# PWR_P5V5.net
KiCad netlist of a schematic drawn in Altium Designer
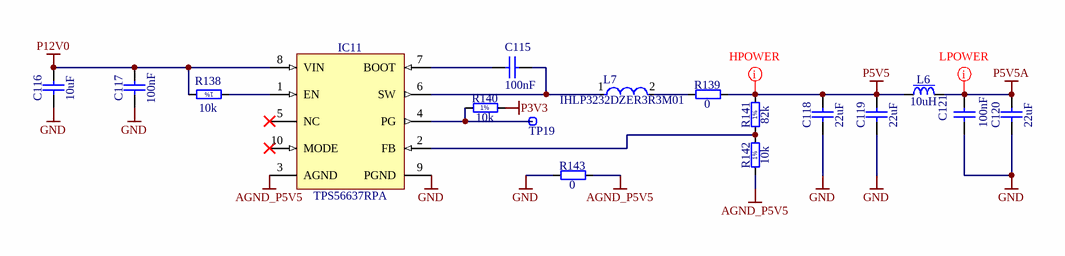
[diagram p0: PWR_P5V5.SchDoc]

(export (version "E")
  (design (tool "Eeschema 10.0.6"))
  (components
    (comp (ref "C115")
      (value "100nF")
      (footprint "CAPC1005X55N")
      (description "Non-polarised capacitor")
      (fields
        (field (name "PART NUMBER") "CC0402_100NF_16V_10%_X5R")
        (field (name "VOLTAGE") "16V")
        (field (name "AUTHOR") "CERN DEM JLC")
      )
      (libsource (lib "Capacitors") (part "Capacitor - non polarized"))
    )
    (comp (ref "C116")
      (value "10uF")
      (footprint "CAPC1608X80N")
      (description "Non-polarised capacitor")
      (fields
        (field (name "PART NUMBER") "CC0603_10UF_10V_10%_X5R")
        (field (name "VOLTAGE") "10V")
        (field (name "AUTHOR") "CERN DEM JLC")
      )
      (libsource (lib "Capacitors") (part "Capacitor - non polarized"))
    )
    (comp (ref "C117")
      (value "100nF")
      (footprint "CAPC1005X55N")
      (description "Non-polarised capacitor")
      (fields
        (field (name "PART NUMBER") "CC0402_100NF_16V_10%_X5R")
        (field (name "VOLTAGE") "16V")
        (field (name "AUTHOR") "CERN DEM JLC")
      )
      (libsource (lib "Capacitors") (part "Capacitor - non polarized"))
    )
    (comp (ref "C118")
      (value "22uF")
      (footprint "CAPC2012X135N")
      (description "Non-polarised capacitor")
      (fields
        (field (name "PART NUMBER") "CC0805_22UF_16V_10%_X5R")
        (field (name "VOLTAGE") "16V")
        (field (name "AUTHOR") "CERN DEM JLC")
      )
      (libsource (lib "Capacitors") (part "Capacitor - non polarized"))
    )
    (comp (ref "C119")
      (value "22uF")
      (footprint "CAPC2012X135N")
      (description "Non-polarised capacitor")
      (fields
        (field (name "PART NUMBER") "CC0805_22UF_16V_10%_X5R")
        (field (name "VOLTAGE") "16V")
        (field (name "AUTHOR") "CERN DEM JLC")
      )
      (libsource (lib "Capacitors") (part "Capacitor - non polarized"))
    )
    (comp (ref "C120")
      (value "22uF")
      (footprint "CAPC2012X135N")
      (description "Non-polarised capacitor")
      (fields
        (field (name "PART NUMBER") "CC0805_22UF_16V_10%_X5R")
        (field (name "VOLTAGE") "16V")
        (field (name "AUTHOR") "CERN DEM JLC")
      )
      (libsource (lib "Capacitors") (part "Capacitor - non polarized"))
    )
    (comp (ref "C121")
      (value "100nF")
      (footprint "CAPC1005X55N")
      (description "Non-polarised capacitor")
      (fields
        (field (name "PART NUMBER") "CC0402_100NF_16V_10%_X5R")
        (field (name "VOLTAGE") "16V")
        (field (name "AUTHOR") "CERN DEM JLC")
      )
      (libsource (lib "Capacitors") (part "Capacitor - non polarized"))
    )
    (comp (ref "IC11")
      (value "TPS56637RPA")
      (footprint "TEXAS_RPA0010A")
      (description "4.5V to 28V Input, 6A Synchronous Buck Converter")
      (fields (field (name "MANUFACTURER") "TEXAS INSTRUMENTS") (field (name "AUTHOR") "CERN DEM BC"))
      (libsource (lib "ICs And Semiconductors") (part "TPS56637RPA"))
    )
    (comp (ref "L6")
      (value "10uH")
      (footprint "IND_MURATA-PS_8400")
      (description "Inductor With Core")
      (fields
        (field (name "PART NUMBER") "IND_10UH_10%_MURATA-PS_8400")
        (field (name "POWER") "950mA")
        (field (name "AUTHOR") "CERN DEM JLC")
      )
      (libsource (lib "Inductors & Transformers") (part "Inductor With Magnetic core"))
    )
    (comp (ref "L7")
      (value "IHLP3232DZER3R3M01")
      (footprint "FP-IHLP-3232DZ-FP_2_413x5-MFG")
      (description "Commercial Inductors, Low DCR Series 3.3uH 9.2 A 17.7mΩ 20%")
      (fields (field (name "TOLERANCE") "20%"))
      (libsource (lib "Altium Content Vault") (part "725321dda6339637d4d059423bc1c3c"))
    )
    (comp (ref "R138")
      (value "10k")
      (footprint "RESC1005X40N")
      (description "Resistor - 1%")
      (fields
        (field (name "PART NUMBER") "R0402_10K_1%_0.0625W_100PPM")
        (field (name "MANUFACTURER") "GENERIC")
        (field (name "AUTHOR") "CERN DEM JLC")
      )
      (libsource (lib "Resistors") (part "Resistor - 1%"))
    )
    (comp (ref "R139")
      (value "0")
      (footprint "RESC3116X80N")
      (description "Resistor")
      (fields
        (field (name "PART NUMBER") "R1206_0R_JUMPER_SEI_HCJ")
        (field (name "MANUFACTURER") "SEI (STACKPOLE ELECTRONICS INC.)")
        (field (name "AUTHOR") "CERN DEM MR")
      )
      (libsource (lib "Resistors") (part "Resistor"))
    )
    (comp (ref "R140")
      (value "10k")
      (footprint "RESC1005X40N")
      (description "Resistor - 1%")
      (fields
        (field (name "PART NUMBER") "R0402_10K_1%_0.0625W_100PPM")
        (field (name "MANUFACTURER") "GENERIC")
        (field (name "AUTHOR") "CERN DEM JLC")
      )
      (libsource (lib "Resistors") (part "Resistor - 1%"))
    )
    (comp (ref "R141")
      (value "82k")
      (footprint "RESC1608X55N")
      (description "Resistor - 1%")
      (fields
        (field (name "PART NUMBER") "R0603_82K_1%_0.1W_100PPM")
        (field (name "MANUFACTURER") "GENERIC")
        (field (name "AUTHOR") "CERN DEM JLC")
      )
      (libsource (lib "Resistors") (part "Resistor - 1%"))
    )
    (comp (ref "R142")
      (value "10k")
      (footprint "RESC1005X40N")
      (description "Resistor - 1%")
      (fields
        (field (name "PART NUMBER") "R0402_10K_1%_0.0625W_100PPM")
        (field (name "MANUFACTURER") "GENERIC")
        (field (name "AUTHOR") "CERN DEM JLC")
      )
      (libsource (lib "Resistors") (part "Resistor - 1%"))
    )
    (comp (ref "R143")
      (value "0")
      (footprint "RESC1005X40N")
      (description "Resistor")
      (fields
        (field (name "PART NUMBER") "R0402_0R_JUMPER")
        (field (name "MANUFACTURER") "GENERIC")
        (field (name "AUTHOR") "CERN DEM JLC")
      )
      (libsource (lib "Resistors") (part "Resistor"))
    )
    (comp (ref "TP19")
      (value "Test Point")
      (footprint "TPS127")
      (fields (field (name "PART NUMBER") "SMD_PAD_1.27X1.27MM") (field (name "AUTHOR") "CERN DEM JLC"))
      (libsource (lib "Eletro-mechanical") (part "Test Point"))
    )
  )
  (nets
    (net (code "1") (name "AGND_P5V5") (class "Default")
      (node (ref "IC11") (pin "3") (pinfunction "AGND_3") (pintype "power_in"))
      (node (ref "R142") (pin "1") (pinfunction "1_1") (pintype "passive"))
      (node (ref "R143") (pin "2") (pinfunction "2_2") (pintype "passive"))
    )
    (net (code "2") (name "GND") (class "Default")
      (node (ref "C116") (pin "1") (pinfunction "1_1") (pintype "passive"))
      (node (ref "C117") (pin "1") (pinfunction "1_1") (pintype "passive"))
      (node (ref "C118") (pin "1") (pinfunction "1_1") (pintype "passive"))
      (node (ref "C119") (pin "1") (pinfunction "1_1") (pintype "passive"))
      (node (ref "C120") (pin "1") (pinfunction "1_1") (pintype "passive"))
      (node (ref "C121") (pin "1") (pinfunction "1_1") (pintype "passive"))
      (node (ref "IC11") (pin "9") (pinfunction "PGND_9") (pintype "power_in"))
      (node (ref "R143") (pin "1") (pinfunction "1_1") (pintype "passive"))
    )
    (net (code "3") (name "Net-(IC11-BOOT)") (class "Default")
      (node (ref "C115") (pin "2") (pinfunction "2_2") (pintype "passive"))
      (node (ref "IC11") (pin "7") (pinfunction "BOOT_7") (pintype "input"))
    )
    (net (code "4") (name "Net-(IC11-EN)") (class "Default")
      (node (ref "IC11") (pin "1") (pinfunction "EN_1") (pintype "input"))
      (node (ref "R138") (pin "1") (pinfunction "1_1") (pintype "passive"))
    )
    (net (code "5") (name "Net-(IC11-FB)") (class "Default")
      (node (ref "IC11") (pin "2") (pinfunction "FB_2") (pintype "input"))
      (node (ref "R141") (pin "1") (pinfunction "1_1") (pintype "passive"))
      (node (ref "R142") (pin "2") (pinfunction "2_2") (pintype "passive"))
    )
    (net (code "6") (name "Net-(IC11-PG)") (class "Default")
      (node (ref "IC11") (pin "4") (pinfunction "PG_4") (pintype "output"))
      (node (ref "R140") (pin "1") (pinfunction "1_1") (pintype "passive"))
      (node (ref "TP19") (pin "1") (pinfunction "1_1") (pintype "bidirectional"))
    )
    (net (code "7") (name "Net-(IC11-SW)") (class "Default")
      (node (ref "C115") (pin "1") (pinfunction "1_1") (pintype "passive"))
      (node (ref "IC11") (pin "6") (pinfunction "SW_6") (pintype "output"))
      (node (ref "L7") (pin "1") (pinfunction "1_1") (pintype "passive"))
    )
    (net (code "8") (name "Net-(L7-Pad2)") (class "Default")
      (node (ref "L7") (pin "2") (pinfunction "2_2") (pintype "passive"))
      (node (ref "R139") (pin "1") (pinfunction "1_1") (pintype "passive"))
    )
    (net (code "9") (name "P3V3") (class "Default")
      (node (ref "R140") (pin "2") (pinfunction "2_2") (pintype "passive"))
    )
    (net (code "10") (name "P5V5") (class "Default")
      (node (ref "C118") (pin "2") (pinfunction "2_2") (pintype "passive"))
      (node (ref "C119") (pin "2") (pinfunction "2_2") (pintype "passive"))
      (node (ref "L6") (pin "1") (pinfunction "1_1") (pintype "passive"))
      (node (ref "R139") (pin "2") (pinfunction "2_2") (pintype "passive"))
      (node (ref "R141") (pin "2") (pinfunction "2_2") (pintype "passive"))
    )
    (net (code "11") (name "P5V5A") (class "Default")
      (node (ref "C120") (pin "2") (pinfunction "2_2") (pintype "passive"))
      (node (ref "C121") (pin "2") (pinfunction "2_2") (pintype "passive"))
      (node (ref "L6") (pin "2") (pinfunction "2_2") (pintype "passive"))
    )
    (net (code "12") (name "P12V0") (class "Default")
      (node (ref "C116") (pin "2") (pinfunction "2_2") (pintype "passive"))
      (node (ref "C117") (pin "2") (pinfunction "2_2") (pintype "passive"))
      (node (ref "IC11") (pin "8") (pinfunction "VIN_8") (pintype "input"))
      (node (ref "R138") (pin "2") (pinfunction "2_2") (pintype "passive"))
    )
    (net (code "13") (name "unconnected-(IC11-MODE-Pad10)") (class "Default")
      (node (ref "IC11") (pin "10") (pinfunction "MODE_10") (pintype "input+no_connect"))
    )
    (net (code "14") (name "unconnected-(IC11-NC-Pad5)") (class "Default")
      (node (ref "IC11") (pin "5") (pinfunction "NC_5") (pintype "passive+no_connect"))
    )
  )
)
